# MasterBoard.net
KiCad netlist of a schematic drawn in EAGLE
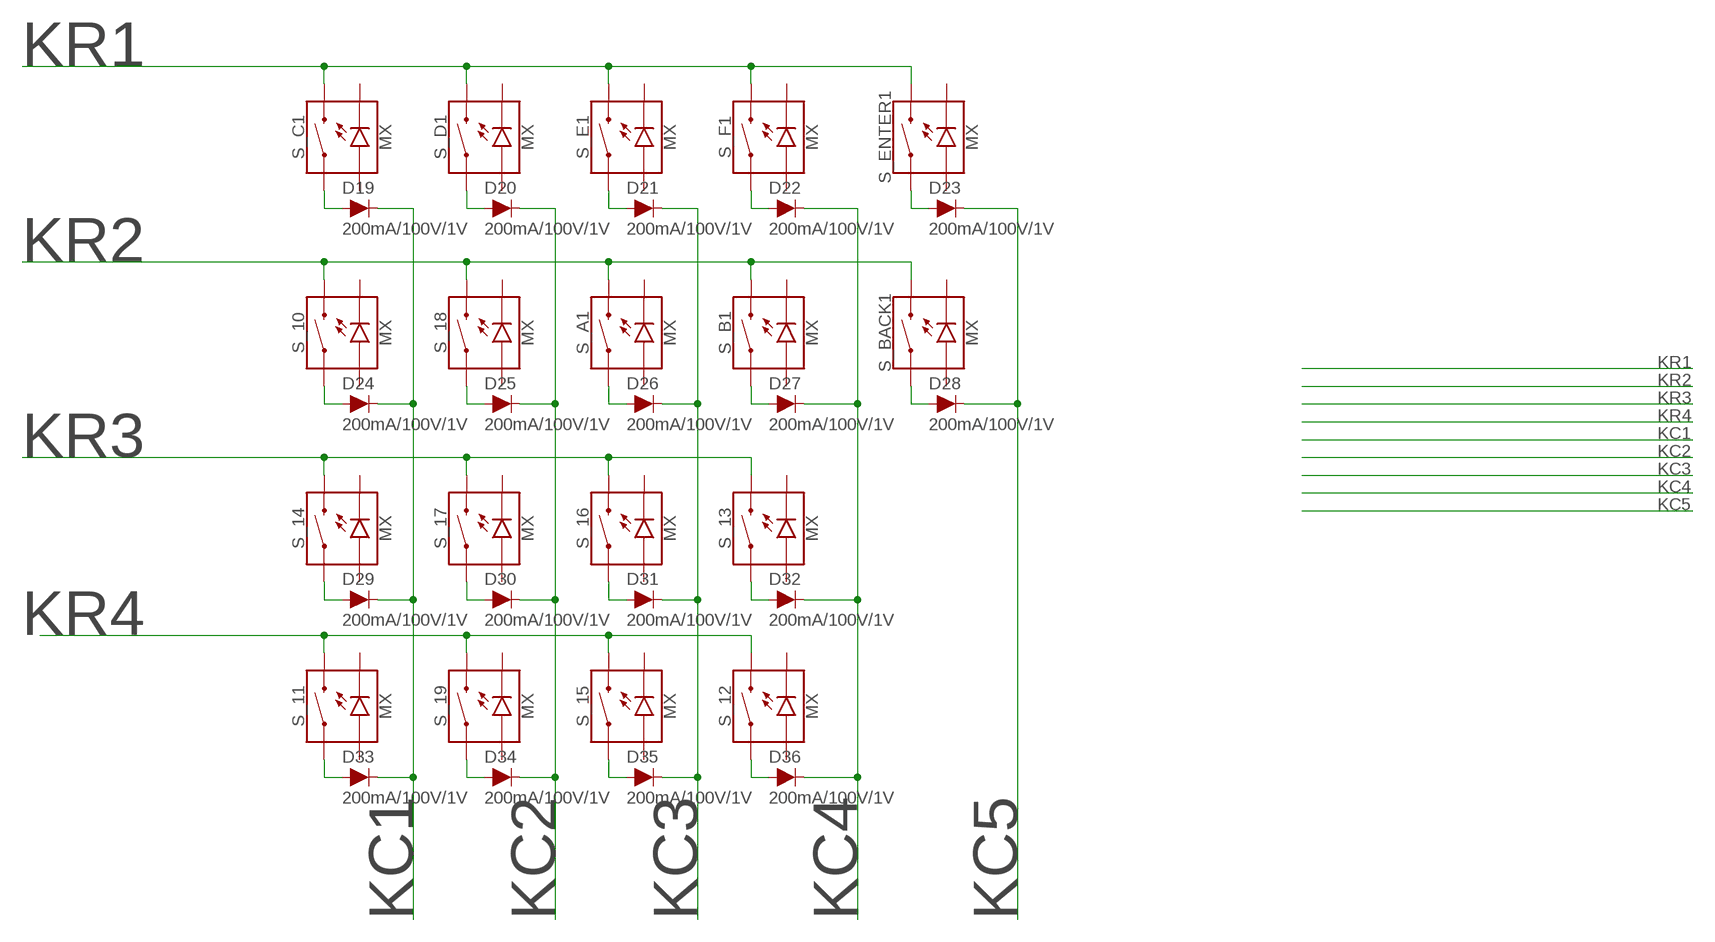
[diagram p0: schematic, sheet 1, part 1 of 2]
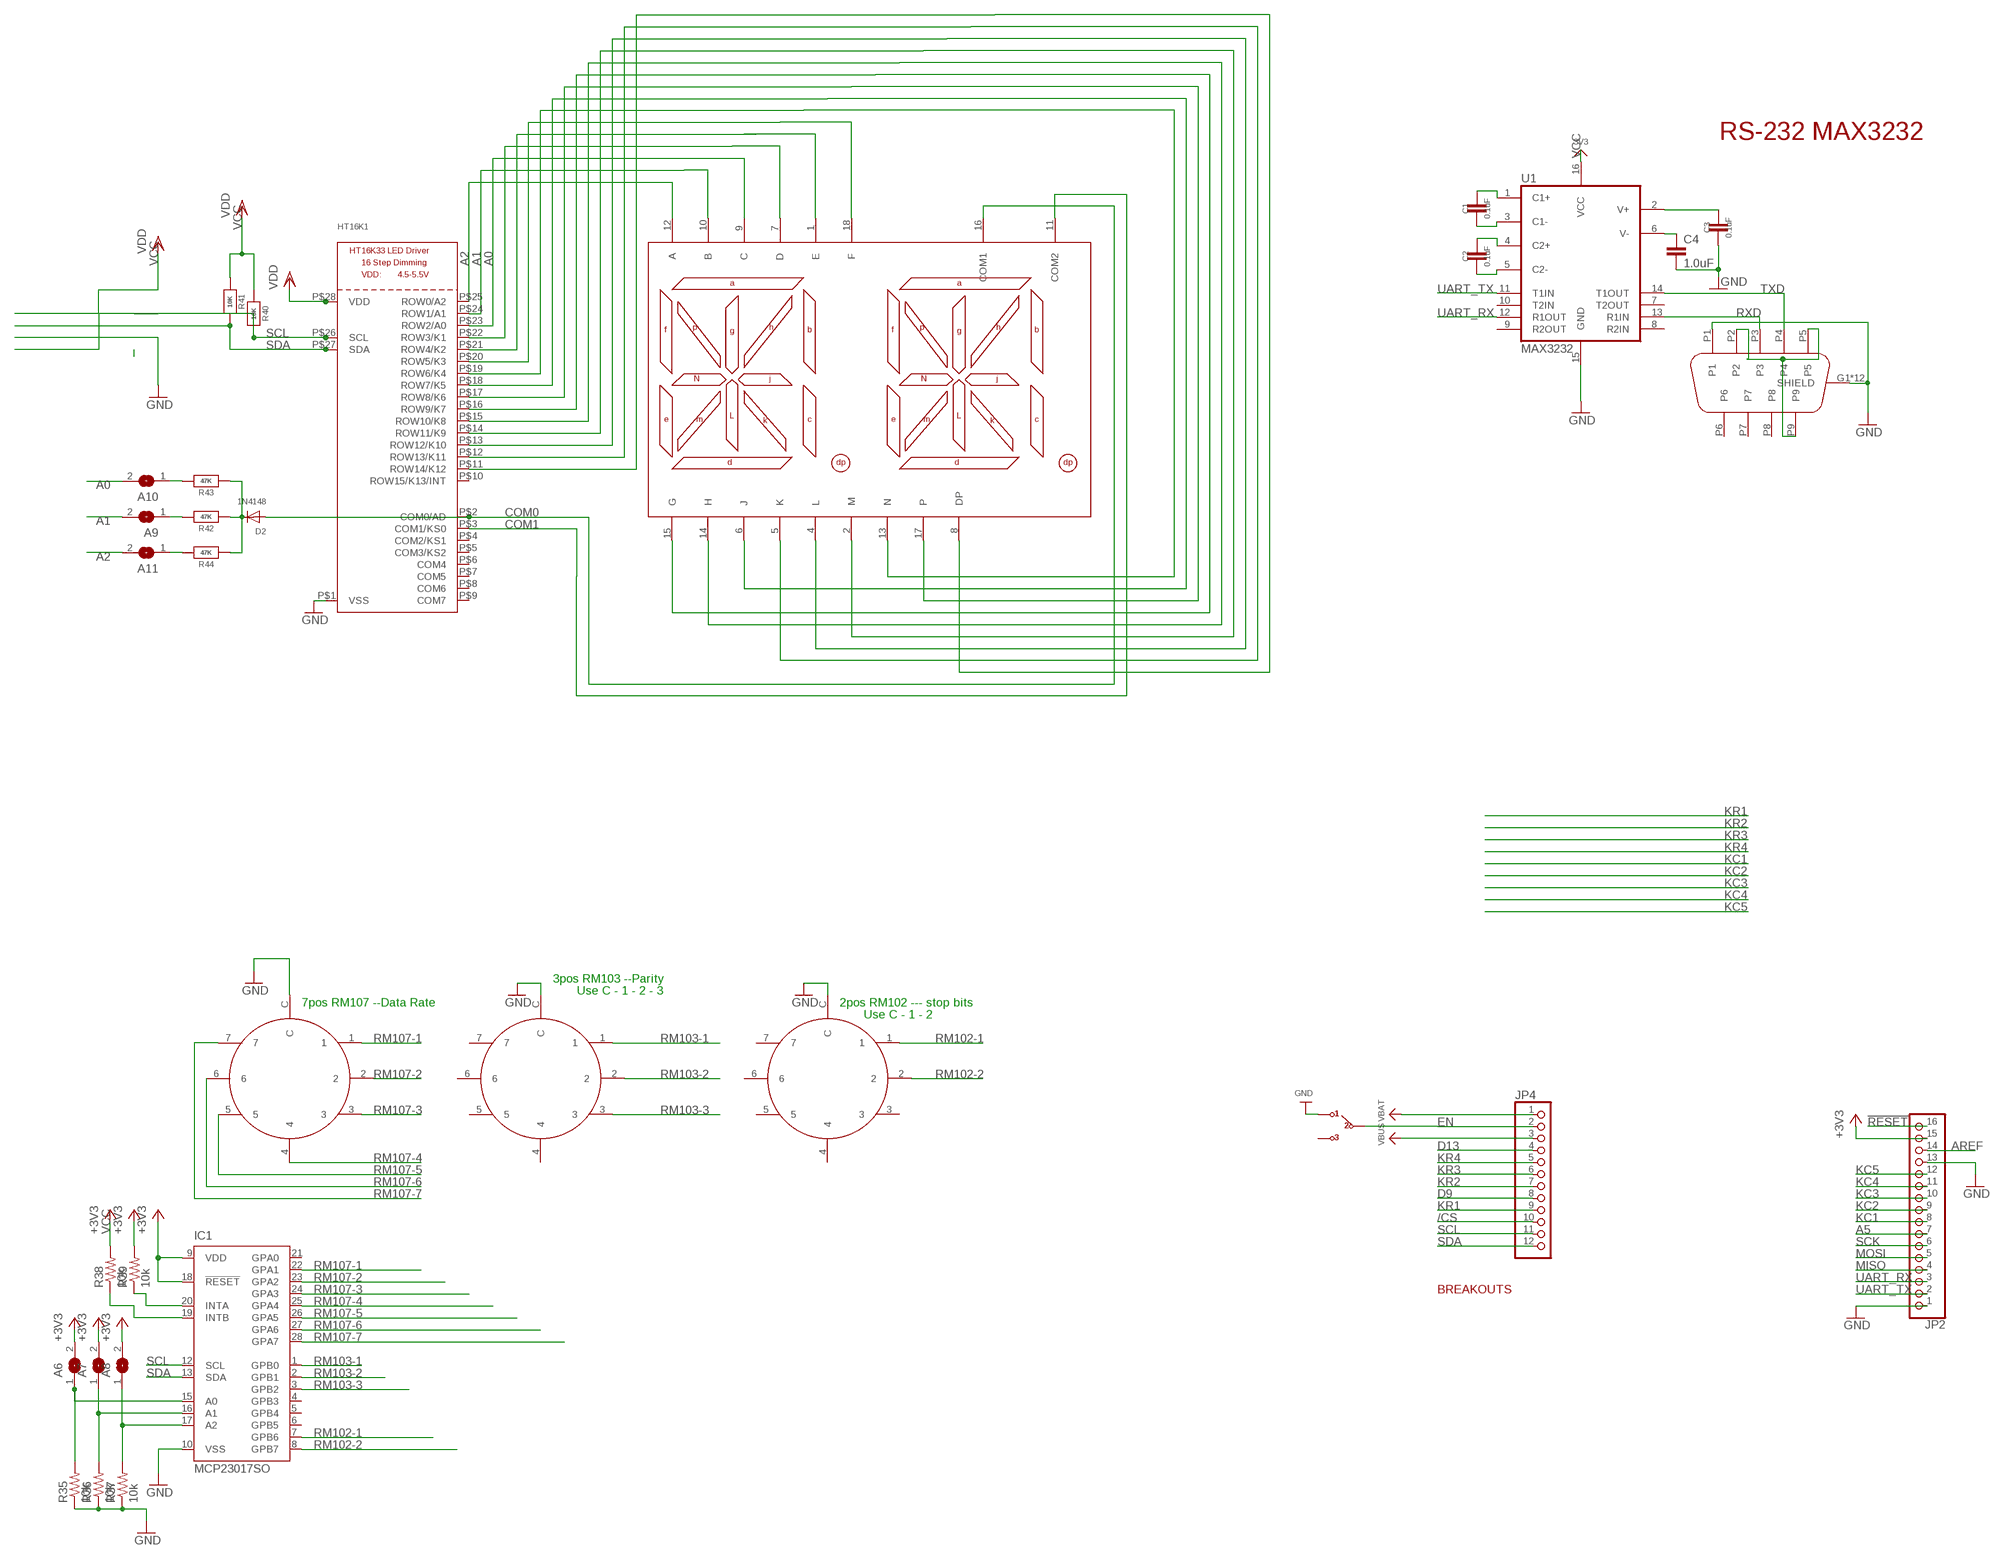
[diagram p1: schematic, sheet 1, part 2 of 2]

(export (version "E")
  (design (tool "Eeschema 10.0.6"))
  (components
    (comp (ref "A6") (value "SJ") (footprint "eagle-import:SJ") (libsource (lib "eagle-import") (part "SJ")))
    (comp (ref "A7") (value "SJ") (footprint "eagle-import:SJ") (libsource (lib "eagle-import") (part "SJ")))
    (comp (ref "A8") (value "SJ") (footprint "eagle-import:SJ") (libsource (lib "eagle-import") (part "SJ")))
    (comp (ref "A9")
      (value "SOLDERJUMPERREFLOW_NOPASTE")
      (footprint "eagle-import:SOLDERJUMPER_REFLOW_NOPASTE")
      (libsource (lib "eagle-import") (part "SOLDERJUMPERREFLOW_NOPASTE"))
    )
    (comp (ref "A10")
      (value "SOLDERJUMPERREFLOW_NOPASTE")
      (footprint "eagle-import:SOLDERJUMPER_REFLOW_NOPASTE")
      (libsource (lib "eagle-import") (part "SOLDERJUMPERREFLOW_NOPASTE"))
    )
    (comp (ref "A11")
      (value "SOLDERJUMPERREFLOW_NOPASTE")
      (footprint "eagle-import:SOLDERJUMPER_REFLOW_NOPASTE")
      (libsource (lib "eagle-import") (part "SOLDERJUMPERREFLOW_NOPASTE"))
    )
    (comp (ref "C1")
      (value "0.1uF")
      (footprint "eagle-import:0805")
      (libsource (lib "eagle-import") (part "1.0UF-0805-25V-10%"))
    )
    (comp (ref "C2")
      (value "0.1uF")
      (footprint "eagle-import:0805")
      (libsource (lib "eagle-import") (part "1.0UF-0805-25V-10%"))
    )
    (comp (ref "C3")
      (value "0.1uF")
      (footprint "eagle-import:0805")
      (libsource (lib "eagle-import") (part "1.0UF-0805-25V-10%"))
    )
    (comp (ref "C4")
      (value "1.0uF")
      (footprint "eagle-import:0805")
      (libsource (lib "eagle-import") (part "1.0UF-0805-25V-10%"))
    )
    (comp (ref "D2")
      (value "1N4148")
      (footprint "eagle-import:SOD-323F")
      (libsource (lib "eagle-import") (part "DIODESOD-323F"))
    )
    (comp (ref "D19")
      (value "200mA/100V/1V")
      (footprint "eagle-import:DIODE-1N4148")
      (libsource (lib "eagle-import") (part "DIODE-1N4148"))
    )
    (comp (ref "D20")
      (value "200mA/100V/1V")
      (footprint "eagle-import:DIODE-1N4148")
      (libsource (lib "eagle-import") (part "DIODE-1N4148"))
    )
    (comp (ref "D21")
      (value "200mA/100V/1V")
      (footprint "eagle-import:DIODE-1N4148")
      (libsource (lib "eagle-import") (part "DIODE-1N4148"))
    )
    (comp (ref "D22")
      (value "200mA/100V/1V")
      (footprint "eagle-import:DIODE-1N4148")
      (libsource (lib "eagle-import") (part "DIODE-1N4148"))
    )
    (comp (ref "D23")
      (value "200mA/100V/1V")
      (footprint "eagle-import:DIODE-1N4148")
      (libsource (lib "eagle-import") (part "DIODE-1N4148"))
    )
    (comp (ref "D24")
      (value "200mA/100V/1V")
      (footprint "eagle-import:DIODE-1N4148")
      (libsource (lib "eagle-import") (part "DIODE-1N4148"))
    )
    (comp (ref "D25")
      (value "200mA/100V/1V")
      (footprint "eagle-import:DIODE-1N4148")
      (libsource (lib "eagle-import") (part "DIODE-1N4148"))
    )
    (comp (ref "D26")
      (value "200mA/100V/1V")
      (footprint "eagle-import:DIODE-1N4148")
      (libsource (lib "eagle-import") (part "DIODE-1N4148"))
    )
    (comp (ref "D27")
      (value "200mA/100V/1V")
      (footprint "eagle-import:DIODE-1N4148")
      (libsource (lib "eagle-import") (part "DIODE-1N4148"))
    )
    (comp (ref "D28")
      (value "200mA/100V/1V")
      (footprint "eagle-import:DIODE-1N4148")
      (libsource (lib "eagle-import") (part "DIODE-1N4148"))
    )
    (comp (ref "D29")
      (value "200mA/100V/1V")
      (footprint "eagle-import:DIODE-1N4148")
      (libsource (lib "eagle-import") (part "DIODE-1N4148"))
    )
    (comp (ref "D30")
      (value "200mA/100V/1V")
      (footprint "eagle-import:DIODE-1N4148")
      (libsource (lib "eagle-import") (part "DIODE-1N4148"))
    )
    (comp (ref "D31")
      (value "200mA/100V/1V")
      (footprint "eagle-import:DIODE-1N4148")
      (libsource (lib "eagle-import") (part "DIODE-1N4148"))
    )
    (comp (ref "D32")
      (value "200mA/100V/1V")
      (footprint "eagle-import:DIODE-1N4148")
      (libsource (lib "eagle-import") (part "DIODE-1N4148"))
    )
    (comp (ref "D33")
      (value "200mA/100V/1V")
      (footprint "eagle-import:DIODE-1N4148")
      (libsource (lib "eagle-import") (part "DIODE-1N4148"))
    )
    (comp (ref "D34")
      (value "200mA/100V/1V")
      (footprint "eagle-import:DIODE-1N4148")
      (libsource (lib "eagle-import") (part "DIODE-1N4148"))
    )
    (comp (ref "D35")
      (value "200mA/100V/1V")
      (footprint "eagle-import:DIODE-1N4148")
      (libsource (lib "eagle-import") (part "DIODE-1N4148"))
    )
    (comp (ref "D36")
      (value "200mA/100V/1V")
      (footprint "eagle-import:DIODE-1N4148")
      (libsource (lib "eagle-import") (part "DIODE-1N4148"))
    )
    (comp (ref "DE9FEMALE1")
      (value "EDGEMOUNTDE9")
      (footprint "eagle-import:DE09S065TLF")
      (libsource (lib "eagle-import") (part "EDGEMOUNTDE9"))
    )
    (comp (ref "HT16K1")
      (value "HT16K33_SOP28_SKINNY")
      (footprint "eagle-import:SOP28_300MIL_SKINNY")
      (libsource (lib "eagle-import") (part "HT16K33_SOP28_SKINNY"))
    )
    (comp (ref "IC1")
      (value "MCP23017SO")
      (footprint "eagle-import:SO28W")
      (libsource (lib "eagle-import") (part "MCP23017SO"))
    )
    (comp (ref "JP2")
      (value "HEADER-1X16ROUND")
      (footprint "eagle-import:1X16_ROUND")
      (libsource (lib "eagle-import") (part "HEADER-1X16ROUND"))
    )
    (comp (ref "JP4")
      (value "HEADER-1X12")
      (footprint "eagle-import:1X12_ROUND")
      (libsource (lib "eagle-import") (part "HEADER-1X12"))
    )
    (comp (ref "R35")
      (value "10k")
      (footprint "eagle-import:M0805")
      (libsource (lib "eagle-import") (part "R-US_M0805"))
    )
    (comp (ref "R36")
      (value "10k")
      (footprint "eagle-import:M0805")
      (libsource (lib "eagle-import") (part "R-US_M0805"))
    )
    (comp (ref "R37")
      (value "10k")
      (footprint "eagle-import:M0805")
      (libsource (lib "eagle-import") (part "R-US_M0805"))
    )
    (comp (ref "R38")
      (value "10k")
      (footprint "eagle-import:M0805")
      (libsource (lib "eagle-import") (part "R-US_M0805"))
    )
    (comp (ref "R39")
      (value "10k")
      (footprint "eagle-import:M0805")
      (libsource (lib "eagle-import") (part "R-US_M0805"))
    )
    (comp (ref "R40")
      (value "10K")
      (footprint "eagle-import:0805-NO")
      (libsource (lib "eagle-import") (part "RESISTOR0805_NOOUTLINE"))
    )
    (comp (ref "R41")
      (value "10K")
      (footprint "eagle-import:0805-NO")
      (libsource (lib "eagle-import") (part "RESISTOR0805_NOOUTLINE"))
    )
    (comp (ref "R42")
      (value "47K")
      (footprint "eagle-import:0805-NO")
      (libsource (lib "eagle-import") (part "RESISTOR0805_NOOUTLINE"))
    )
    (comp (ref "R43")
      (value "47K")
      (footprint "eagle-import:0805-NO")
      (libsource (lib "eagle-import") (part "RESISTOR0805_NOOUTLINE"))
    )
    (comp (ref "R44")
      (value "47K")
      (footprint "eagle-import:0805-NO")
      (libsource (lib "eagle-import") (part "RESISTOR0805_NOOUTLINE"))
    )
    (comp (ref "S_10")
      (value "MX")
      (footprint "eagle-import:CHERRY-MX-LED")
      (libsource (lib "eagle-import") (part "MOMENTARY-SWITCH-SPST-LED-PTH-CHERRY"))
    )
    (comp (ref "S_11")
      (value "MX")
      (footprint "eagle-import:CHERRY-MX-LED")
      (libsource (lib "eagle-import") (part "MOMENTARY-SWITCH-SPST-LED-PTH-CHERRY"))
    )
    (comp (ref "S_12")
      (value "MX")
      (footprint "eagle-import:CHERRY-MX-LED")
      (libsource (lib "eagle-import") (part "MOMENTARY-SWITCH-SPST-LED-PTH-CHERRY"))
    )
    (comp (ref "S_13")
      (value "MX")
      (footprint "eagle-import:CHERRY-MX-LED")
      (libsource (lib "eagle-import") (part "MOMENTARY-SWITCH-SPST-LED-PTH-CHERRY"))
    )
    (comp (ref "S_14")
      (value "MX")
      (footprint "eagle-import:CHERRY-MX-LED")
      (libsource (lib "eagle-import") (part "MOMENTARY-SWITCH-SPST-LED-PTH-CHERRY"))
    )
    (comp (ref "S_15")
      (value "MX")
      (footprint "eagle-import:CHERRY-MX-LED")
      (libsource (lib "eagle-import") (part "MOMENTARY-SWITCH-SPST-LED-PTH-CHERRY"))
    )
    (comp (ref "S_16")
      (value "MX")
      (footprint "eagle-import:CHERRY-MX-LED")
      (libsource (lib "eagle-import") (part "MOMENTARY-SWITCH-SPST-LED-PTH-CHERRY"))
    )
    (comp (ref "S_17")
      (value "MX")
      (footprint "eagle-import:CHERRY-MX-LED")
      (libsource (lib "eagle-import") (part "MOMENTARY-SWITCH-SPST-LED-PTH-CHERRY"))
    )
    (comp (ref "S_18")
      (value "MX")
      (footprint "eagle-import:CHERRY-MX-LED")
      (libsource (lib "eagle-import") (part "MOMENTARY-SWITCH-SPST-LED-PTH-CHERRY"))
    )
    (comp (ref "S_19")
      (value "MX")
      (footprint "eagle-import:CHERRY-MX-LED")
      (libsource (lib "eagle-import") (part "MOMENTARY-SWITCH-SPST-LED-PTH-CHERRY"))
    )
    (comp (ref "S_A1")
      (value "MX")
      (footprint "eagle-import:CHERRY-MX-LED")
      (libsource (lib "eagle-import") (part "MOMENTARY-SWITCH-SPST-LED-PTH-CHERRY"))
    )
    (comp (ref "S_B1")
      (value "MX")
      (footprint "eagle-import:CHERRY-MX-LED")
      (libsource (lib "eagle-import") (part "MOMENTARY-SWITCH-SPST-LED-PTH-CHERRY"))
    )
    (comp (ref "S_BACK1")
      (value "MX")
      (footprint "eagle-import:CHERRY-MX-LED")
      (libsource (lib "eagle-import") (part "MOMENTARY-SWITCH-SPST-LED-PTH-CHERRY"))
    )
    (comp (ref "S_C1")
      (value "MX")
      (footprint "eagle-import:CHERRY-MX-LED")
      (libsource (lib "eagle-import") (part "MOMENTARY-SWITCH-SPST-LED-PTH-CHERRY"))
    )
    (comp (ref "S_D1")
      (value "MX")
      (footprint "eagle-import:CHERRY-MX-LED")
      (libsource (lib "eagle-import") (part "MOMENTARY-SWITCH-SPST-LED-PTH-CHERRY"))
    )
    (comp (ref "S_E1")
      (value "MX")
      (footprint "eagle-import:CHERRY-MX-LED")
      (libsource (lib "eagle-import") (part "MOMENTARY-SWITCH-SPST-LED-PTH-CHERRY"))
    )
    (comp (ref "S_ENTER1")
      (value "MX")
      (footprint "eagle-import:CHERRY-MX-LED")
      (libsource (lib "eagle-import") (part "MOMENTARY-SWITCH-SPST-LED-PTH-CHERRY"))
    )
    (comp (ref "S_F1")
      (value "MX")
      (footprint "eagle-import:CHERRY-MX-LED")
      (libsource (lib "eagle-import") (part "MOMENTARY-SWITCH-SPST-LED-PTH-CHERRY"))
    )
    (comp (ref "U$11")
      (value "BIG14SEG")
      (footprint "eagle-import:HDSP")
      (libsource (lib "eagle-import") (part "BIG14SEG"))
    )
    (comp (ref "U$12")
      (value "RM107772BCB")
      (footprint "eagle-import:RM107772BCB")
      (libsource (lib "eagle-import") (part "RM107772BCB"))
    )
    (comp (ref "U$15")
      (value "OS102011MA1QN1")
      (footprint "eagle-import:OS102011MA1QN1")
      (libsource (lib "eagle-import") (part "OS102011MA1QN1"))
    )
    (comp (ref "U$17")
      (value "RM107772BCB")
      (footprint "eagle-import:RM107772BCB")
      (libsource (lib "eagle-import") (part "RM107772BCB"))
    )
    (comp (ref "U$18")
      (value "RM107772BCB")
      (footprint "eagle-import:RM107772BCB")
      (libsource (lib "eagle-import") (part "RM107772BCB"))
    )
    (comp (ref "U1")
      (value "MAX3232")
      (footprint "eagle-import:SO16")
      (libsource (lib "eagle-import") (part "MAX2323SOIC16"))
    )
  )
  (nets
    (net (code "1") (name "+3V3") (class "Default")
      (node (ref "A6") (pin "2") (pinfunction "2_2") (pintype "passive"))
      (node (ref "A7") (pin "2") (pinfunction "2_2") (pintype "passive"))
      (node (ref "A8") (pin "2") (pinfunction "2_2") (pintype "passive"))
      (node (ref "HT16K1") (pin "P$28") (pinfunction "VDD_P$28") (pintype "bidirectional"))
      (node (ref "IC1") (pin "18") (pinfunction "~{RESET}_18") (pintype "input"))
      (node (ref "IC1") (pin "9") (pinfunction "VDD_9") (pintype "power_in"))
      (node (ref "JP2") (pin "15") (pinfunction "15_15") (pintype "passive"))
      (node (ref "R38") (pin "2") (pinfunction "2_2") (pintype "passive"))
      (node (ref "R39") (pin "2") (pinfunction "2_2") (pintype "passive"))
      (node (ref "R40") (pin "1") (pinfunction "1_1") (pintype "passive"))
      (node (ref "R41") (pin "1") (pinfunction "1_1") (pintype "passive"))
      (node (ref "U1") (pin "16") (pinfunction "VCC_16") (pintype "bidirectional"))
    )
    (net (code "2") (name "/A0") (class "Default")
      (node (ref "A10") (pin "2") (pinfunction "2_2") (pintype "passive"))
      (node (ref "HT16K1") (pin "P$23") (pinfunction "ROW2/A0_P$23") (pintype "bidirectional"))
      (node (ref "U$11") (pin "9") (pinfunction "C_9") (pintype "bidirectional"))
    )
    (net (code "3") (name "/A1") (class "Default")
      (node (ref "A9") (pin "2") (pinfunction "2_2") (pintype "passive"))
      (node (ref "HT16K1") (pin "P$24") (pinfunction "ROW1/A1_P$24") (pintype "bidirectional"))
      (node (ref "U$11") (pin "10") (pinfunction "B_10") (pintype "bidirectional"))
    )
    (net (code "4") (name "/A2") (class "Default")
      (node (ref "A11") (pin "2") (pinfunction "2_2") (pintype "passive"))
      (node (ref "HT16K1") (pin "P$25") (pinfunction "ROW0/A2_P$25") (pintype "bidirectional"))
      (node (ref "U$11") (pin "12") (pinfunction "A_12") (pintype "bidirectional"))
    )
    (net (code "5") (name "/A5") (class "Default")
      (node (ref "JP2") (pin "7") (pinfunction "7_7") (pintype "passive"))
    )
    (net (code "6") (name "/AREF") (class "Default")
      (node (ref "JP2") (pin "14") (pinfunction "14_14") (pintype "passive"))
    )
    (net (code "7") (name "/COM0") (class "Default")
      (node (ref "D2") (pin "A") (pinfunction "A_A") (pintype "passive"))
      (node (ref "HT16K1") (pin "P$2") (pinfunction "COM0/AD_P$2") (pintype "bidirectional"))
      (node (ref "U$11") (pin "16") (pinfunction "COM1_16") (pintype "bidirectional"))
    )
    (net (code "8") (name "/COM1") (class "Default")
      (node (ref "HT16K1") (pin "P$3") (pinfunction "COM1/KS0_P$3") (pintype "bidirectional"))
      (node (ref "U$11") (pin "11") (pinfunction "COM2_11") (pintype "bidirectional"))
    )
    (net (code "9") (name "/D9") (class "Default")
      (node (ref "JP4") (pin "8") (pinfunction "8_8") (pintype "passive"))
    )
    (net (code "10") (name "/D13") (class "Default")
      (node (ref "JP4") (pin "4") (pinfunction "4_4") (pintype "passive"))
    )
    (net (code "11") (name "/EN") (class "Default")
      (node (ref "JP4") (pin "2") (pinfunction "2_2") (pintype "passive"))
      (node (ref "U$15") (pin "P$2") (pinfunction "P$2_P$2") (pintype "bidirectional"))
    )
    (net (code "12") (name "/KC1") (class "Default")
      (node (ref "D19") (pin "C") (pinfunction "C_C") (pintype "passive"))
      (node (ref "D24") (pin "C") (pinfunction "C_C") (pintype "passive"))
      (node (ref "D29") (pin "C") (pinfunction "C_C") (pintype "passive"))
      (node (ref "D33") (pin "C") (pinfunction "C_C") (pintype "passive"))
      (node (ref "JP2") (pin "8") (pinfunction "8_8") (pintype "passive"))
    )
    (net (code "13") (name "/KC2") (class "Default")
      (node (ref "D20") (pin "C") (pinfunction "C_C") (pintype "passive"))
      (node (ref "D25") (pin "C") (pinfunction "C_C") (pintype "passive"))
      (node (ref "D30") (pin "C") (pinfunction "C_C") (pintype "passive"))
      (node (ref "D34") (pin "C") (pinfunction "C_C") (pintype "passive"))
      (node (ref "JP2") (pin "9") (pinfunction "9_9") (pintype "passive"))
    )
    (net (code "14") (name "/KC3") (class "Default")
      (node (ref "D21") (pin "C") (pinfunction "C_C") (pintype "passive"))
      (node (ref "D26") (pin "C") (pinfunction "C_C") (pintype "passive"))
      (node (ref "D31") (pin "C") (pinfunction "C_C") (pintype "passive"))
      (node (ref "D35") (pin "C") (pinfunction "C_C") (pintype "passive"))
      (node (ref "JP2") (pin "10") (pinfunction "10_10") (pintype "passive"))
    )
    (net (code "15") (name "/KC4") (class "Default")
      (node (ref "D22") (pin "C") (pinfunction "C_C") (pintype "passive"))
      (node (ref "D27") (pin "C") (pinfunction "C_C") (pintype "passive"))
      (node (ref "D32") (pin "C") (pinfunction "C_C") (pintype "passive"))
      (node (ref "D36") (pin "C") (pinfunction "C_C") (pintype "passive"))
      (node (ref "JP2") (pin "11") (pinfunction "11_11") (pintype "passive"))
    )
    (net (code "16") (name "/KC5") (class "Default")
      (node (ref "D23") (pin "C") (pinfunction "C_C") (pintype "passive"))
      (node (ref "D28") (pin "C") (pinfunction "C_C") (pintype "passive"))
      (node (ref "JP2") (pin "12") (pinfunction "12_12") (pintype "passive"))
    )
    (net (code "17") (name "/KR1") (class "Default")
      (node (ref "JP4") (pin "9") (pinfunction "9_9") (pintype "passive"))
      (node (ref "S_C1") (pin "S2") (pinfunction "2_S2") (pintype "passive"))
      (node (ref "S_D1") (pin "S2") (pinfunction "2_S2") (pintype "passive"))
      (node (ref "S_E1") (pin "S2") (pinfunction "2_S2") (pintype "passive"))
      (node (ref "S_ENTER1") (pin "S2") (pinfunction "2_S2") (pintype "passive"))
      (node (ref "S_F1") (pin "S2") (pinfunction "2_S2") (pintype "passive"))
    )
    (net (code "18") (name "/KR2") (class "Default")
      (node (ref "JP4") (pin "7") (pinfunction "7_7") (pintype "passive"))
      (node (ref "S_10") (pin "S2") (pinfunction "2_S2") (pintype "passive"))
      (node (ref "S_18") (pin "S2") (pinfunction "2_S2") (pintype "passive"))
      (node (ref "S_A1") (pin "S2") (pinfunction "2_S2") (pintype "passive"))
      (node (ref "S_B1") (pin "S2") (pinfunction "2_S2") (pintype "passive"))
      (node (ref "S_BACK1") (pin "S2") (pinfunction "2_S2") (pintype "passive"))
    )
    (net (code "19") (name "/KR3") (class "Default")
      (node (ref "JP4") (pin "6") (pinfunction "6_6") (pintype "passive"))
      (node (ref "S_13") (pin "S2") (pinfunction "2_S2") (pintype "passive"))
      (node (ref "S_14") (pin "S2") (pinfunction "2_S2") (pintype "passive"))
      (node (ref "S_16") (pin "S2") (pinfunction "2_S2") (pintype "passive"))
      (node (ref "S_17") (pin "S2") (pinfunction "2_S2") (pintype "passive"))
    )
    (net (code "20") (name "/KR4") (class "Default")
      (node (ref "JP4") (pin "5") (pinfunction "5_5") (pintype "passive"))
      (node (ref "S_11") (pin "S2") (pinfunction "2_S2") (pintype "passive"))
      (node (ref "S_12") (pin "S2") (pinfunction "2_S2") (pintype "passive"))
      (node (ref "S_15") (pin "S2") (pinfunction "2_S2") (pintype "passive"))
      (node (ref "S_19") (pin "S2") (pinfunction "2_S2") (pintype "passive"))
    )
    (net (code "21") (name "/MISO") (class "Default")
      (node (ref "JP2") (pin "4") (pinfunction "4_4") (pintype "passive"))
    )
    (net (code "22") (name "/MOSI") (class "Default")
      (node (ref "JP2") (pin "5") (pinfunction "5_5") (pintype "passive"))
    )
    (net (code "23") (name "/RM102-1") (class "Default")
      (node (ref "IC1") (pin "7") (pinfunction "GPB6_7") (pintype "bidirectional"))
      (node (ref "U$18") (pin "1") (pinfunction "1_1") (pintype "bidirectional"))
    )
    (net (code "24") (name "/RM102-2") (class "Default")
      (node (ref "IC1") (pin "8") (pinfunction "GPB7_8") (pintype "bidirectional"))
      (node (ref "U$18") (pin "2") (pinfunction "2_2") (pintype "bidirectional"))
    )
    (net (code "25") (name "/RM103-1") (class "Default")
      (node (ref "IC1") (pin "1") (pinfunction "GPB0_1") (pintype "bidirectional"))
      (node (ref "U$17") (pin "1") (pinfunction "1_1") (pintype "bidirectional"))
    )
    (net (code "26") (name "/RM103-2") (class "Default")
      (node (ref "IC1") (pin "2") (pinfunction "GPB1_2") (pintype "bidirectional"))
      (node (ref "U$17") (pin "2") (pinfunction "2_2") (pintype "bidirectional"))
    )
    (net (code "27") (name "/RM103-3") (class "Default")
      (node (ref "IC1") (pin "3") (pinfunction "GPB2_3") (pintype "bidirectional"))
      (node (ref "U$17") (pin "3") (pinfunction "3_3") (pintype "bidirectional"))
    )
    (net (code "28") (name "/RM107-1") (class "Default")
      (node (ref "IC1") (pin "22") (pinfunction "GPA1_22") (pintype "bidirectional"))
      (node (ref "U$12") (pin "1") (pinfunction "1_1") (pintype "bidirectional"))
    )
    (net (code "29") (name "/RM107-2") (class "Default")
      (node (ref "IC1") (pin "23") (pinfunction "GPA2_23") (pintype "bidirectional"))
      (node (ref "U$12") (pin "2") (pinfunction "2_2") (pintype "bidirectional"))
    )
    (net (code "30") (name "/RM107-3") (class "Default")
      (node (ref "IC1") (pin "24") (pinfunction "GPA3_24") (pintype "bidirectional"))
      (node (ref "U$12") (pin "3") (pinfunction "3_3") (pintype "bidirectional"))
    )
    (net (code "31") (name "/RM107-4") (class "Default")
      (node (ref "IC1") (pin "25") (pinfunction "GPA4_25") (pintype "bidirectional"))
      (node (ref "U$12") (pin "4") (pinfunction "4_4") (pintype "bidirectional"))
    )
    (net (code "32") (name "/RM107-5") (class "Default")
      (node (ref "IC1") (pin "26") (pinfunction "GPA5_26") (pintype "bidirectional"))
      (node (ref "U$12") (pin "5") (pinfunction "5_5") (pintype "bidirectional"))
    )
    (net (code "33") (name "/RM107-6") (class "Default")
      (node (ref "IC1") (pin "27") (pinfunction "GPA6_27") (pintype "bidirectional"))
      (node (ref "U$12") (pin "6") (pinfunction "6_6") (pintype "bidirectional"))
    )
    (net (code "34") (name "/RM107-7") (class "Default")
      (node (ref "IC1") (pin "28") (pinfunction "GPA7_28") (pintype "bidirectional"))
      (node (ref "U$12") (pin "7") (pinfunction "7_7") (pintype "bidirectional"))
    )
    (net (code "35") (name "/RXD") (class "Default")
      (node (ref "DE9FEMALE1") (pin "P3") (pinfunction "P3_P3") (pintype "bidirectional"))
      (node (ref "U1") (pin "13") (pinfunction "R1IN_13") (pintype "input"))
    )
    (net (code "36") (name "/SCK") (class "Default")
      (node (ref "JP2") (pin "6") (pinfunction "6_6") (pintype "passive"))
    )
    (net (code "37") (name "/SCL") (class "Default")
      (node (ref "HT16K1") (pin "P$26") (pinfunction "SCL_P$26") (pintype "bidirectional"))
      (node (ref "IC1") (pin "12") (pinfunction "SCL_12") (pintype "input"))
      (node (ref "JP4") (pin "11") (pinfunction "11_11") (pintype "passive"))
      (node (ref "R40") (pin "2") (pinfunction "2_2") (pintype "passive"))
    )
    (net (code "38") (name "/SDA") (class "Default")
      (node (ref "HT16K1") (pin "P$27") (pinfunction "SDA_P$27") (pintype "bidirectional"))
      (node (ref "IC1") (pin "13") (pinfunction "SDA_13") (pintype "bidirectional"))
      (node (ref "JP4") (pin "12") (pinfunction "12_12") (pintype "passive"))
      (node (ref "R41") (pin "2") (pinfunction "2_2") (pintype "passive"))
    )
    (net (code "39") (name "/TXD") (class "Default")
      (node (ref "DE9FEMALE1") (pin "P4") (pinfunction "P4_P4") (pintype "bidirectional"))
      (node (ref "U1") (pin "14") (pinfunction "T1OUT_14") (pintype "output"))
    )
    (net (code "40") (name "/UART_RX") (class "Default")
      (node (ref "JP2") (pin "3") (pinfunction "3_3") (pintype "passive"))
      (node (ref "U1") (pin "12") (pinfunction "R1OUT_12") (pintype "output"))
    )
    (net (code "41") (name "/UART_TX") (class "Default")
      (node (ref "JP2") (pin "2") (pinfunction "2_2") (pintype "passive"))
      (node (ref "U1") (pin "11") (pinfunction "T1IN_11") (pintype "input"))
    )
    (net (code "42") (name "/{slash}CS") (class "Default")
      (node (ref "JP4") (pin "10") (pinfunction "10_10") (pintype "passive"))
    )
    (net (code "43") (name "/~{RESET}") (class "Default")
      (node (ref "JP2") (pin "16") (pinfunction "16_16") (pintype "passive"))
    )
    (net (code "44") (name "GND") (class "Default")
      (node (ref "C3") (pin "2") (pinfunction "2_2") (pintype "passive"))
      (node (ref "C4") (pin "2") (pinfunction "2_2") (pintype "passive"))
      (node (ref "DE9FEMALE1") (pin "G1") (pinfunction "SHIELD_G1") (pintype "bidirectional"))
      (node (ref "DE9FEMALE1") (pin "G10") (pinfunction "SHIELD_G10") (pintype "bidirectional"))
      (node (ref "DE9FEMALE1") (pin "G11") (pinfunction "SHIELD_G11") (pintype "bidirectional"))
      (node (ref "DE9FEMALE1") (pin "G12") (pinfunction "SHIELD_G12") (pintype "bidirectional"))
      (node (ref "DE9FEMALE1") (pin "G2") (pinfunction "SHIELD_G2") (pintype "bidirectional"))
      (node (ref "DE9FEMALE1") (pin "G3") (pinfunction "SHIELD_G3") (pintype "bidirectional"))
      (node (ref "DE9FEMALE1") (pin "G4") (pinfunction "SHIELD_G4") (pintype "bidirectional"))
      (node (ref "DE9FEMALE1") (pin "G5") (pinfunction "SHIELD_G5") (pintype "bidirectional"))
      (node (ref "DE9FEMALE1") (pin "G6") (pinfunction "SHIELD_G6") (pintype "bidirectional"))
      (node (ref "DE9FEMALE1") (pin "G7") (pinfunction "SHIELD_G7") (pintype "bidirectional"))
      (node (ref "DE9FEMALE1") (pin "G8") (pinfunction "SHIELD_G8") (pintype "bidirectional"))
      (node (ref "DE9FEMALE1") (pin "G9") (pinfunction "SHIELD_G9") (pintype "bidirectional"))
      (node (ref "DE9FEMALE1") (pin "P1") (pinfunction "P1_P1") (pintype "bidirectional"))
      (node (ref "HT16K1") (pin "P$1") (pinfunction "VSS_P$1") (pintype "bidirectional"))
      (node (ref "IC1") (pin "10") (pinfunction "VSS_10") (pintype "power_in"))
      (node (ref "JP2") (pin "1") (pinfunction "1_1") (pintype "passive"))
      (node (ref "JP2") (pin "13") (pinfunction "13_13") (pintype "passive"))
      (node (ref "R35") (pin "1") (pinfunction "1_1") (pintype "passive"))
      (node (ref "R36") (pin "1") (pinfunction "1_1") (pintype "passive"))
      (node (ref "R37") (pin "1") (pinfunction "1_1") (pintype "passive"))
      (node (ref "U$12") (pin "C") (pinfunction "C_C") (pintype "bidirectional"))
      (node (ref "U$15") (pin "P$1") (pinfunction "P$1_P$1") (pintype "bidirectional"))
      (node (ref "U$17") (pin "C") (pinfunction "C_C") (pintype "bidirectional"))
      (node (ref "U$18") (pin "C") (pinfunction "C_C") (pintype "bidirectional"))
      (node (ref "U1") (pin "15") (pinfunction "GND_15") (pintype "bidirectional"))
    )
    (net (code "45") (name "Net-(A9-Pad1)") (class "Default")
      (node (ref "A9") (pin "1") (pinfunction "1_1") (pintype "passive"))
      (node (ref "R42") (pin "2") (pinfunction "2_2") (pintype "passive"))
    )
    (net (code "46") (name "Net-(A10-Pad1)") (class "Default")
      (node (ref "A10") (pin "1") (pinfunction "1_1") (pintype "passive"))
      (node (ref "R43") (pin "2") (pinfunction "2_2") (pintype "passive"))
    )
    (net (code "47") (name "Net-(A11-Pad1)") (class "Default")
      (node (ref "A11") (pin "1") (pinfunction "1_1") (pintype "passive"))
      (node (ref "R44") (pin "2") (pinfunction "2_2") (pintype "passive"))
    )
    (net (code "48") (name "Net-(D2-PadC)") (class "Default")
      (node (ref "D2") (pin "C") (pinfunction "C_C") (pintype "passive"))
      (node (ref "R42") (pin "1") (pinfunction "1_1") (pintype "passive"))
      (node (ref "R43") (pin "1") (pinfunction "1_1") (pintype "passive"))
      (node (ref "R44") (pin "1") (pinfunction "1_1") (pintype "passive"))
    )
    (net (code "49") (name "Net-(DE9FEMALE1-PadP2)") (class "Default")
      (node (ref "DE9FEMALE1") (pin "P2") (pinfunction "P2_P2") (pintype "bidirectional"))
      (node (ref "DE9FEMALE1") (pin "P5") (pinfunction "P5_P5") (pintype "bidirectional"))
      (node (ref "DE9FEMALE1") (pin "P9") (pinfunction "P9_P9") (pintype "bidirectional"))
    )
    (net (code "50") (name "Net-(HT16K1-ROW3{slash}K1)") (class "Default")
      (node (ref "HT16K1") (pin "P$22") (pinfunction "ROW3/K1_P$22") (pintype "bidirectional"))
      (node (ref "U$11") (pin "7") (pinfunction "D_7") (pintype "bidirectional"))
    )
    (net (code "51") (name "Net-(HT16K1-ROW4{slash}K2)") (class "Default")
      (node (ref "HT16K1") (pin "P$21") (pinfunction "ROW4/K2_P$21") (pintype "bidirectional"))
      (node (ref "U$11") (pin "1") (pinfunction "E_1") (pintype "bidirectional"))
    )
    (net (code "52") (name "Net-(HT16K1-ROW5{slash}K3)") (class "Default")
      (node (ref "HT16K1") (pin "P$20") (pinfunction "ROW5/K3_P$20") (pintype "bidirectional"))
      (node (ref "U$11") (pin "18") (pinfunction "F_18") (pintype "bidirectional"))
    )
    (net (code "53") (name "Net-(HT16K1-ROW6{slash}K4)") (class "Default")
      (node (ref "HT16K1") (pin "P$19") (pinfunction "ROW6/K4_P$19") (pintype "bidirectional"))
      (node (ref "U$11") (pin "13") (pinfunction "N_13") (pintype "bidirectional"))
    )
    (net (code "54") (name "Net-(HT16K1-ROW7{slash}K5)") (class "Default")
      (node (ref "HT16K1") (pin "P$18") (pinfunction "ROW7/K5_P$18") (pintype "bidirectional"))
      (node (ref "U$11") (pin "6") (pinfunction "J_6") (pintype "bidirectional"))
    )
    (net (code "55") (name "Net-(HT16K1-ROW8{slash}K6)") (class "Default")
      (node (ref "HT16K1") (pin "P$17") (pinfunction "ROW8/K6_P$17") (pintype "bidirectional"))
      (node (ref "U$11") (pin "17") (pinfunction "P_17") (pintype "bidirectional"))
    )
    (net (code "56") (name "Net-(HT16K1-ROW9{slash}K7)") (class "Default")
      (node (ref "HT16K1") (pin "P$16") (pinfunction "ROW9/K7_P$16") (pintype "bidirectional"))
      (node (ref "U$11") (pin "15") (pinfunction "G_15") (pintype "bidirectional"))
    )
    (net (code "57") (name "Net-(HT16K1-ROW10{slash}K8)") (class "Default")
      (node (ref "HT16K1") (pin "P$15") (pinfunction "ROW10/K8_P$15") (pintype "bidirectional"))
      (node (ref "U$11") (pin "14") (pinfunction "H_14") (pintype "bidirectional"))
    )
    (net (code "58") (name "Net-(HT16K1-ROW11{slash}K9)") (class "Default")
      (node (ref "HT16K1") (pin "P$14") (pinfunction "ROW11/K9_P$14") (pintype "bidirectional"))
      (node (ref "U$11") (pin "2") (pinfunction "M_2") (pintype "bidirectional"))
    )
    (net (code "59") (name "Net-(HT16K1-ROW12{slash}K10)") (class "Default")
      (node (ref "HT16K1") (pin "P$13") (pinfunction "ROW12/K10_P$13") (pintype "bidirectional"))
      (node (ref "U$11") (pin "4") (pinfunction "L_4") (pintype "bidirectional"))
    )
    (net (code "60") (name "Net-(HT16K1-ROW13{slash}K11)") (class "Default")
      (node (ref "HT16K1") (pin "P$12") (pinfunction "ROW13/K11_P$12") (pintype "bidirectional"))
      (node (ref "U$11") (pin "5") (pinfunction "K_5") (pintype "bidirectional"))
    )
    (net (code "61") (name "Net-(HT16K1-ROW14{slash}K12)") (class "Default")
      (node (ref "HT16K1") (pin "P$11") (pinfunction "ROW14/K12_P$11") (pintype "bidirectional"))
      (node (ref "U$11") (pin "8") (pinfunction "DP_8") (pintype "bidirectional"))
    )
    (net (code "62") (name "Net-(IC1-A0)") (class "Default")
      (node (ref "A6") (pin "1") (pinfunction "1_1") (pintype "passive"))
      (node (ref "IC1") (pin "15") (pinfunction "A0_15") (pintype "input"))
      (node (ref "R35") (pin "2") (pinfunction "2_2") (pintype "passive"))
    )
    (net (code "63") (name "Net-(IC1-A1)") (class "Default")
      (node (ref "A7") (pin "1") (pinfunction "1_1") (pintype "passive"))
      (node (ref "IC1") (pin "16") (pinfunction "A1_16") (pintype "input"))
      (node (ref "R36") (pin "2") (pinfunction "2_2") (pintype "passive"))
    )
    (net (code "64") (name "Net-(IC1-A2)") (class "Default")
      (node (ref "A8") (pin "1") (pinfunction "1_1") (pintype "passive"))
      (node (ref "IC1") (pin "17") (pinfunction "A2_17") (pintype "input"))
      (node (ref "R37") (pin "2") (pinfunction "2_2") (pintype "passive"))
    )
    (net (code "65") (name "Net-(IC1-INTA)") (class "Default")
      (node (ref "IC1") (pin "20") (pinfunction "INTA_20") (pintype "output"))
      (node (ref "R39") (pin "1") (pinfunction "1_1") (pintype "passive"))
    )
    (net (code "66") (name "Net-(IC1-INTB)") (class "Default")
      (node (ref "IC1") (pin "19") (pinfunction "INTB_19") (pintype "output"))
      (node (ref "R38") (pin "1") (pinfunction "1_1") (pintype "passive"))
    )
    (net (code "67") (name "Net-(S_10-1)") (class "Default")
      (node (ref "D24") (pin "A") (pinfunction "A_A") (pintype "passive"))
      (node (ref "S_10") (pin "S1") (pinfunction "1_S1") (pintype "passive"))
    )
    (net (code "68") (name "Net-(S_11-1)") (class "Default")
      (node (ref "D33") (pin "A") (pinfunction "A_A") (pintype "passive"))
      (node (ref "S_11") (pin "S1") (pinfunction "1_S1") (pintype "passive"))
    )
    (net (code "69") (name "Net-(S_12-1)") (class "Default")
      (node (ref "D36") (pin "A") (pinfunction "A_A") (pintype "passive"))
      (node (ref "S_12") (pin "S1") (pinfunction "1_S1") (pintype "passive"))
    )
    (net (code "70") (name "Net-(S_13-1)") (class "Default")
      (node (ref "D32") (pin "A") (pinfunction "A_A") (pintype "passive"))
      (node (ref "S_13") (pin "S1") (pinfunction "1_S1") (pintype "passive"))
    )
    (net (code "71") (name "Net-(S_14-1)") (class "Default")
      (node (ref "D29") (pin "A") (pinfunction "A_A") (pintype "passive"))
      (node (ref "S_14") (pin "S1") (pinfunction "1_S1") (pintype "passive"))
    )
    (net (code "72") (name "Net-(S_15-1)") (class "Default")
      (node (ref "D35") (pin "A") (pinfunction "A_A") (pintype "passive"))
      (node (ref "S_15") (pin "S1") (pinfunction "1_S1") (pintype "passive"))
    )
    (net (code "73") (name "Net-(S_16-1)") (class "Default")
      (node (ref "D31") (pin "A") (pinfunction "A_A") (pintype "passive"))
      (node (ref "S_16") (pin "S1") (pinfunction "1_S1") (pintype "passive"))
    )
    (net (code "74") (name "Net-(S_17-1)") (class "Default")
      (node (ref "D30") (pin "A") (pinfunction "A_A") (pintype "passive"))
      (node (ref "S_17") (pin "S1") (pinfunction "1_S1") (pintype "passive"))
    )
    (net (code "75") (name "Net-(S_18-1)") (class "Default")
      (node (ref "D25") (pin "A") (pinfunction "A_A") (pintype "passive"))
      (node (ref "S_18") (pin "S1") (pinfunction "1_S1") (pintype "passive"))
    )
    (net (code "76") (name "Net-(S_19-1)") (class "Default")
      (node (ref "D34") (pin "A") (pinfunction "A_A") (pintype "passive"))
      (node (ref "S_19") (pin "S1") (pinfunction "1_S1") (pintype "passive"))
    )
    (net (code "77") (name "Net-(S_A1-1)") (class "Default")
      (node (ref "D26") (pin "A") (pinfunction "A_A") (pintype "passive"))
      (node (ref "S_A1") (pin "S1") (pinfunction "1_S1") (pintype "passive"))
    )
    (net (code "78") (name "Net-(S_B1-1)") (class "Default")
      (node (ref "D27") (pin "A") (pinfunction "A_A") (pintype "passive"))
      (node (ref "S_B1") (pin "S1") (pinfunction "1_S1") (pintype "passive"))
    )
    (net (code "79") (name "Net-(S_BACK1-1)") (class "Default")
      (node (ref "D28") (pin "A") (pinfunction "A_A") (pintype "passive"))
      (node (ref "S_BACK1") (pin "S1") (pinfunction "1_S1") (pintype "passive"))
    )
    (net (code "80") (name "Net-(S_C1-1)") (class "Default")
      (node (ref "D19") (pin "A") (pinfunction "A_A") (pintype "passive"))
      (node (ref "S_C1") (pin "S1") (pinfunction "1_S1") (pintype "passive"))
    )
    (net (code "81") (name "Net-(S_D1-1)") (class "Default")
      (node (ref "D20") (pin "A") (pinfunction "A_A") (pintype "passive"))
      (node (ref "S_D1") (pin "S1") (pinfunction "1_S1") (pintype "passive"))
    )
    (net (code "82") (name "Net-(S_E1-1)") (class "Default")
      (node (ref "D21") (pin "A") (pinfunction "A_A") (pintype "passive"))
      (node (ref "S_E1") (pin "S1") (pinfunction "1_S1") (pintype "passive"))
    )
    (net (code "83") (name "Net-(S_ENTER1-1)") (class "Default")
      (node (ref "D23") (pin "A") (pinfunction "A_A") (pintype "passive"))
      (node (ref "S_ENTER1") (pin "S1") (pinfunction "1_S1") (pintype "passive"))
    )
    (net (code "84") (name "Net-(S_F1-1)") (class "Default")
      (node (ref "D22") (pin "A") (pinfunction "A_A") (pintype "passive"))
      (node (ref "S_F1") (pin "S1") (pinfunction "1_S1") (pintype "passive"))
    )
    (net (code "85") (name "Net-(U1-C1+)") (class "Default")
      (node (ref "C1") (pin "1") (pinfunction "1_1") (pintype "passive"))
      (node (ref "U1") (pin "1") (pinfunction "C1+_1") (pintype "bidirectional"))
    )
    (net (code "86") (name "Net-(U1-C1-)") (class "Default")
      (node (ref "C1") (pin "2") (pinfunction "2_2") (pintype "passive"))
      (node (ref "U1") (pin "3") (pinfunction "C1-_3") (pintype "bidirectional"))
    )
    (net (code "87") (name "Net-(U1-C2+)") (class "Default")
      (node (ref "C2") (pin "1") (pinfunction "1_1") (pintype "passive"))
      (node (ref "U1") (pin "4") (pinfunction "C2+_4") (pintype "bidirectional"))
    )
    (net (code "88") (name "Net-(U1-C2-)") (class "Default")
      (node (ref "C2") (pin "2") (pinfunction "2_2") (pintype "passive"))
      (node (ref "U1") (pin "5") (pinfunction "C2-_5") (pintype "bidirectional"))
    )
    (net (code "89") (name "Net-(U1-V+)") (class "Default")
      (node (ref "C3") (pin "1") (pinfunction "1_1") (pintype "passive"))
      (node (ref "U1") (pin "2") (pinfunction "V+_2") (pintype "bidirectional"))
    )
    (net (code "90") (name "Net-(U1-V-)") (class "Default")
      (node (ref "C4") (pin "1") (pinfunction "1_1") (pintype "passive"))
      (node (ref "U1") (pin "6") (pinfunction "V-_6") (pintype "bidirectional"))
    )
    (net (code "91") (name "VBAT") (class "Default")
      (node (ref "JP4") (pin "1") (pinfunction "1_1") (pintype "passive"))
    )
    (net (code "92") (name "VBUS") (class "Default")
      (node (ref "JP4") (pin "3") (pinfunction "3_3") (pintype "passive"))
    )
    (net (code "93") (name "unconnected-(DE9FEMALE1-PadP6)") (class "Default")
      (node (ref "DE9FEMALE1") (pin "P6") (pinfunction "P6_P6") (pintype "bidirectional"))
    )
    (net (code "94") (name "unconnected-(DE9FEMALE1-PadP7)") (class "Default")
      (node (ref "DE9FEMALE1") (pin "P7") (pinfunction "P7_P7") (pintype "bidirectional"))
    )
    (net (code "95") (name "unconnected-(DE9FEMALE1-PadP8)") (class "Default")
      (node (ref "DE9FEMALE1") (pin "P8") (pinfunction "P8_P8") (pintype "bidirectional"))
    )
    (net (code "96") (name "unconnected-(HT16K1-COM2{slash}KS1-PadP$4)") (class "Default")
      (node (ref "HT16K1") (pin "P$4") (pinfunction "COM2/KS1_P$4") (pintype "bidirectional"))
    )
    (net (code "97") (name "unconnected-(HT16K1-COM3{slash}KS2-PadP$5)") (class "Default")
      (node (ref "HT16K1") (pin "P$5") (pinfunction "COM3/KS2_P$5") (pintype "bidirectional"))
    )
    (net (code "98") (name "unconnected-(HT16K1-COM4-PadP$6)") (class "Default")
      (node (ref "HT16K1") (pin "P$6") (pinfunction "COM4_P$6") (pintype "bidirectional"))
    )
    (net (code "99") (name "unconnected-(HT16K1-COM5-PadP$7)") (class "Default")
      (node (ref "HT16K1") (pin "P$7") (pinfunction "COM5_P$7") (pintype "bidirectional"))
    )
    (net (code "100") (name "unconnected-(HT16K1-COM6-PadP$8)") (class "Default")
      (node (ref "HT16K1") (pin "P$8") (pinfunction "COM6_P$8") (pintype "bidirectional"))
    )
    (net (code "101") (name "unconnected-(HT16K1-COM7-PadP$9)") (class "Default")
      (node (ref "HT16K1") (pin "P$9") (pinfunction "COM7_P$9") (pintype "bidirectional"))
    )
    (net (code "102") (name "unconnected-(HT16K1-ROW15{slash}K13{slash}INT-PadP$10)") (class "Default")
      (node (ref "HT16K1") (pin "P$10") (pinfunction "ROW15/K13/INT_P$10") (pintype "bidirectional"))
    )
    (net (code "103") (name "unconnected-(IC1-GPA0-Pad21)") (class "Default")
      (node (ref "IC1") (pin "21") (pinfunction "GPA0_21") (pintype "bidirectional"))
    )
    (net (code "104") (name "unconnected-(IC1-GPB3-Pad4)") (class "Default")
      (node (ref "IC1") (pin "4") (pinfunction "GPB3_4") (pintype "bidirectional"))
    )
    (net (code "105") (name "unconnected-(IC1-GPB4-Pad5)") (class "Default")
      (node (ref "IC1") (pin "5") (pinfunction "GPB4_5") (pintype "bidirectional"))
    )
    (net (code "106") (name "unconnected-(IC1-GPB5-Pad6)") (class "Default")
      (node (ref "IC1") (pin "6") (pinfunction "GPB5_6") (pintype "bidirectional"))
    )
    (net (code "107") (name "unconnected-(S_10-C-PadK)") (class "Default")
      (node (ref "S_10") (pin "K") (pinfunction "C_K") (pintype "passive"))
    )
    (net (code "108") (name "unconnected-(S_10-PadA)") (class "Default")
      (node (ref "S_10") (pin "A") (pinfunction "A_A") (pintype "passive"))
    )
    (net (code "109") (name "unconnected-(S_11-C-PadK)") (class "Default")
      (node (ref "S_11") (pin "K") (pinfunction "C_K") (pintype "passive"))
    )
    (net (code "110") (name "unconnected-(S_11-PadA)") (class "Default")
      (node (ref "S_11") (pin "A") (pinfunction "A_A") (pintype "passive"))
    )
    (net (code "111") (name "unconnected-(S_12-C-PadK)") (class "Default")
      (node (ref "S_12") (pin "K") (pinfunction "C_K") (pintype "passive"))
    )
    (net (code "112") (name "unconnected-(S_12-PadA)") (class "Default")
      (node (ref "S_12") (pin "A") (pinfunction "A_A") (pintype "passive"))
    )
    (net (code "113") (name "unconnected-(S_13-C-PadK)") (class "Default")
      (node (ref "S_13") (pin "K") (pinfunction "C_K") (pintype "passive"))
    )
    (net (code "114") (name "unconnected-(S_13-PadA)") (class "Default")
      (node (ref "S_13") (pin "A") (pinfunction "A_A") (pintype "passive"))
    )
    (net (code "115") (name "unconnected-(S_14-C-PadK)") (class "Default")
      (node (ref "S_14") (pin "K") (pinfunction "C_K") (pintype "passive"))
    )
    (net (code "116") (name "unconnected-(S_14-PadA)") (class "Default")
      (node (ref "S_14") (pin "A") (pinfunction "A_A") (pintype "passive"))
    )
    (net (code "117") (name "unconnected-(S_15-C-PadK)") (class "Default")
      (node (ref "S_15") (pin "K") (pinfunction "C_K") (pintype "passive"))
    )
    (net (code "118") (name "unconnected-(S_15-PadA)") (class "Default")
      (node (ref "S_15") (pin "A") (pinfunction "A_A") (pintype "passive"))
    )
    (net (code "119") (name "unconnected-(S_16-C-PadK)") (class "Default")
      (node (ref "S_16") (pin "K") (pinfunction "C_K") (pintype "passive"))
    )
    (net (code "120") (name "unconnected-(S_16-PadA)") (class "Default")
      (node (ref "S_16") (pin "A") (pinfunction "A_A") (pintype "passive"))
    )
    (net (code "121") (name "unconnected-(S_17-C-PadK)") (class "Default")
      (node (ref "S_17") (pin "K") (pinfunction "C_K") (pintype "passive"))
    )
    (net (code "122") (name "unconnected-(S_17-PadA)") (class "Default")
      (node (ref "S_17") (pin "A") (pinfunction "A_A") (pintype "passive"))
    )
    (net (code "123") (name "unconnected-(S_18-C-PadK)") (class "Default")
      (node (ref "S_18") (pin "K") (pinfunction "C_K") (pintype "passive"))
    )
    (net (code "124") (name "unconnected-(S_18-PadA)") (class "Default")
      (node (ref "S_18") (pin "A") (pinfunction "A_A") (pintype "passive"))
    )
    (net (code "125") (name "unconnected-(S_19-C-PadK)") (class "Default")
      (node (ref "S_19") (pin "K") (pinfunction "C_K") (pintype "passive"))
    )
    (net (code "126") (name "unconnected-(S_19-PadA)") (class "Default")
      (node (ref "S_19") (pin "A") (pinfunction "A_A") (pintype "passive"))
    )
    (net (code "127") (name "unconnected-(S_A1-C-PadK)") (class "Default")
      (node (ref "S_A1") (pin "K") (pinfunction "C_K") (pintype "passive"))
    )
    (net (code "128") (name "unconnected-(S_A1-PadA)") (class "Default")
      (node (ref "S_A1") (pin "A") (pinfunction "A_A") (pintype "passive"))
    )
    (net (code "129") (name "unconnected-(S_B1-C-PadK)") (class "Default")
      (node (ref "S_B1") (pin "K") (pinfunction "C_K") (pintype "passive"))
    )
    (net (code "130") (name "unconnected-(S_B1-PadA)") (class "Default")
      (node (ref "S_B1") (pin "A") (pinfunction "A_A") (pintype "passive"))
    )
    (net (code "131") (name "unconnected-(S_BACK1-C-PadK)") (class "Default")
      (node (ref "S_BACK1") (pin "K") (pinfunction "C_K") (pintype "passive"))
    )
    (net (code "132") (name "unconnected-(S_BACK1-PadA)") (class "Default")
      (node (ref "S_BACK1") (pin "A") (pinfunction "A_A") (pintype "passive"))
    )
    (net (code "133") (name "unconnected-(S_C1-C-PadK)") (class "Default")
      (node (ref "S_C1") (pin "K") (pinfunction "C_K") (pintype "passive"))
    )
    (net (code "134") (name "unconnected-(S_C1-PadA)") (class "Default")
      (node (ref "S_C1") (pin "A") (pinfunction "A_A") (pintype "passive"))
    )
    (net (code "135") (name "unconnected-(S_D1-C-PadK)") (class "Default")
      (node (ref "S_D1") (pin "K") (pinfunction "C_K") (pintype "passive"))
    )
    (net (code "136") (name "unconnected-(S_D1-PadA)") (class "Default")
      (node (ref "S_D1") (pin "A") (pinfunction "A_A") (pintype "passive"))
    )
    (net (code "137") (name "unconnected-(S_E1-C-PadK)") (class "Default")
      (node (ref "S_E1") (pin "K") (pinfunction "C_K") (pintype "passive"))
    )
    (net (code "138") (name "unconnected-(S_E1-PadA)") (class "Default")
      (node (ref "S_E1") (pin "A") (pinfunction "A_A") (pintype "passive"))
    )
    (net (code "139") (name "unconnected-(S_ENTER1-C-PadK)") (class "Default")
      (node (ref "S_ENTER1") (pin "K") (pinfunction "C_K") (pintype "passive"))
    )
    (net (code "140") (name "unconnected-(S_ENTER1-PadA)") (class "Default")
      (node (ref "S_ENTER1") (pin "A") (pinfunction "A_A") (pintype "passive"))
    )
    (net (code "141") (name "unconnected-(S_F1-C-PadK)") (class "Default")
      (node (ref "S_F1") (pin "K") (pinfunction "C_K") (pintype "passive"))
    )
    (net (code "142") (name "unconnected-(S_F1-PadA)") (class "Default")
      (node (ref "S_F1") (pin "A") (pinfunction "A_A") (pintype "passive"))
    )
    (net (code "143") (name "unconnected-(U$15-CASE-PadCASE1)") (class "Default")
      (node (ref "U$15") (pin "CASE1") (pinfunction "CASE_CASE1") (pintype "no_connect"))
    )
    (net (code "144") (name "unconnected-(U$15-CASE-PadCASE2)") (class "Default")
      (node (ref "U$15") (pin "CASE2") (pinfunction "CASE_CASE2") (pintype "no_connect"))
    )
    (net (code "145") (name "unconnected-(U$15-PadP$3)") (class "Default")
      (node (ref "U$15") (pin "P$3") (pinfunction "P$3_P$3") (pintype "bidirectional"))
    )
    (net (code "146") (name "unconnected-(U$17-Pad4)") (class "Default")
      (node (ref "U$17") (pin "4") (pinfunction "4_4") (pintype "bidirectional"))
    )
    (net (code "147") (name "unconnected-(U$17-Pad5)") (class "Default")
      (node (ref "U$17") (pin "5") (pinfunction "5_5") (pintype "bidirectional"))
    )
    (net (code "148") (name "unconnected-(U$17-Pad6)") (class "Default")
      (node (ref "U$17") (pin "6") (pinfunction "6_6") (pintype "bidirectional"))
    )
    (net (code "149") (name "unconnected-(U$17-Pad7)") (class "Default")
      (node (ref "U$17") (pin "7") (pinfunction "7_7") (pintype "bidirectional"))
    )
    (net (code "150") (name "unconnected-(U$18-Pad3)") (class "Default")
      (node (ref "U$18") (pin "3") (pinfunction "3_3") (pintype "bidirectional"))
    )
    (net (code "151") (name "unconnected-(U$18-Pad4)") (class "Default")
      (node (ref "U$18") (pin "4") (pinfunction "4_4") (pintype "bidirectional"))
    )
    (net (code "152") (name "unconnected-(U$18-Pad5)") (class "Default")
      (node (ref "U$18") (pin "5") (pinfunction "5_5") (pintype "bidirectional"))
    )
    (net (code "153") (name "unconnected-(U$18-Pad6)") (class "Default")
      (node (ref "U$18") (pin "6") (pinfunction "6_6") (pintype "bidirectional"))
    )
    (net (code "154") (name "unconnected-(U$18-Pad7)") (class "Default")
      (node (ref "U$18") (pin "7") (pinfunction "7_7") (pintype "bidirectional"))
    )
    (net (code "155") (name "unconnected-(U1-R2IN-Pad8)") (class "Default")
      (node (ref "U1") (pin "8") (pinfunction "R2IN_8") (pintype "input"))
    )
    (net (code "156") (name "unconnected-(U1-R2OUT-Pad9)") (class "Default")
      (node (ref "U1") (pin "9") (pinfunction "R2OUT_9") (pintype "output"))
    )
    (net (code "157") (name "unconnected-(U1-T2IN-Pad10)") (class "Default")
      (node (ref "U1") (pin "10") (pinfunction "T2IN_10") (pintype "input"))
    )
    (net (code "158") (name "unconnected-(U1-T2OUT-Pad7)") (class "Default")
      (node (ref "U1") (pin "7") (pinfunction "T2OUT_7") (pintype "output"))
    )
  )
)
